# RJ45-2.net
KiCad netlist of a schematic drawn in Altium Designer
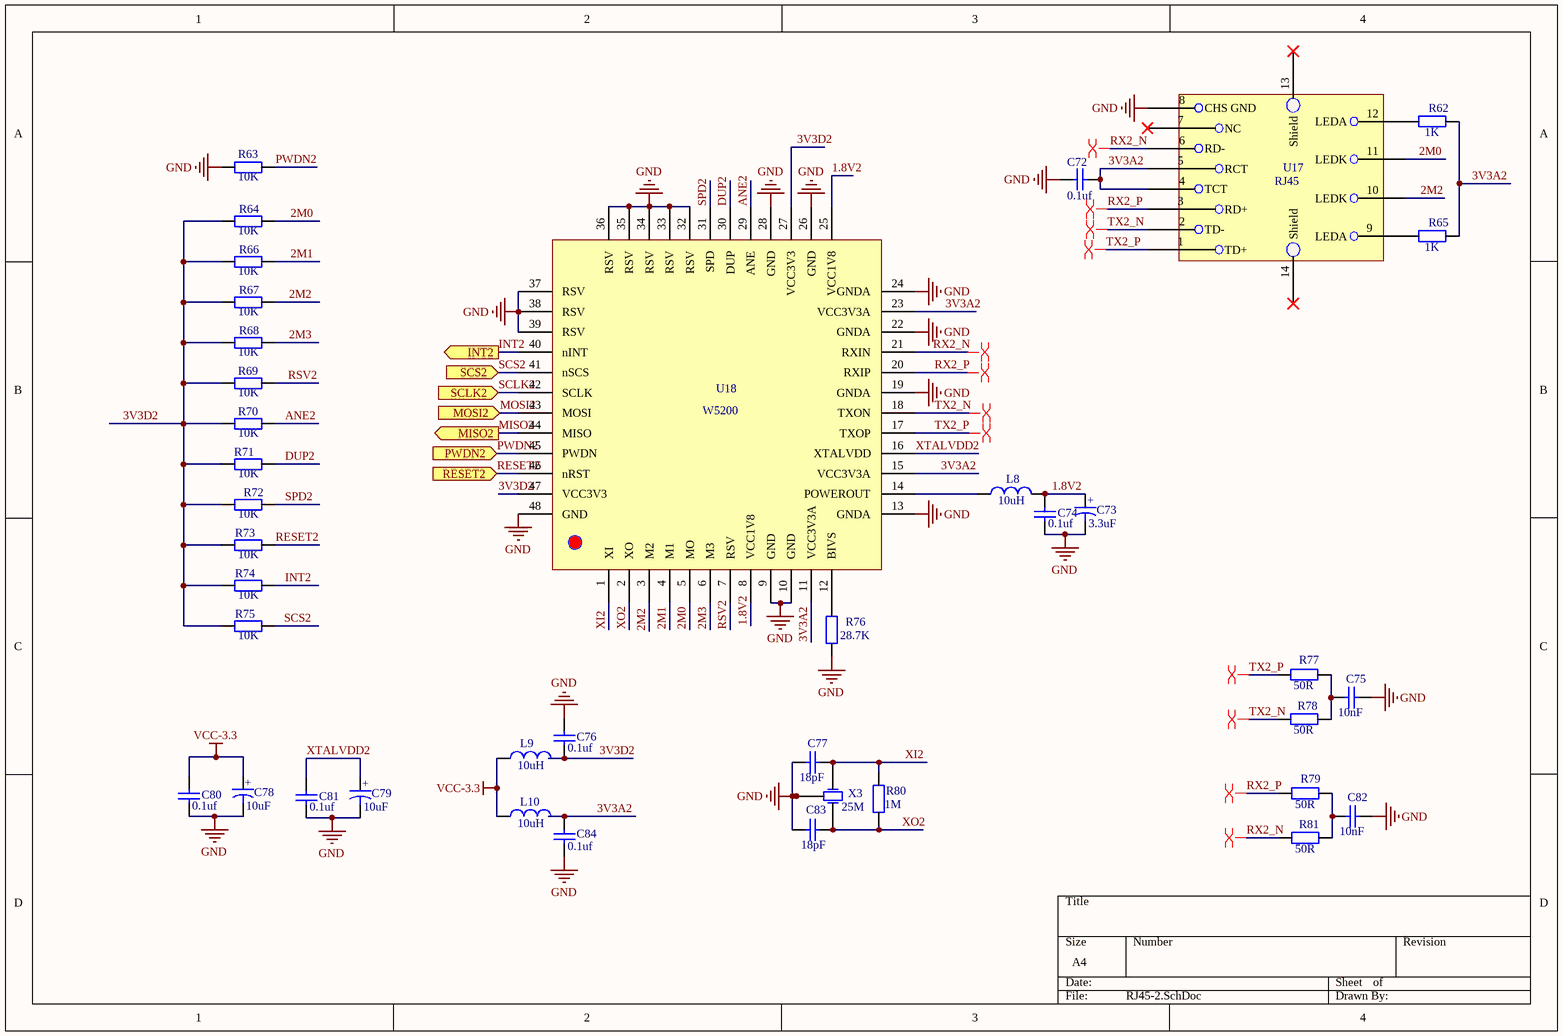
[diagram p0: RJ45-2.SchDoc]

(export (version "E")
  (design (tool "Eeschema 10.0.6"))
  (components
    (comp (ref "C72")
      (value "0.1uf")
      (footprint "0603")
      (fields (field (name "Comment") "Capacitor-0603"))
      (libsource (lib "原理图库") (part "Capacitor-0603"))
    )
    (comp (ref "C73")
      (value "3.3uF")
      (footprint "钽电容1206（A3216）")
      (fields (field (name "ALTIUM_UNNAMED_1") "+") (field (name "Comment") "电解电容"))
      (libsource (lib "原理图库") (part "电解电容"))
    )
    (comp (ref "C74")
      (value "0.1uf")
      (footprint "0603")
      (fields (field (name "Comment") "Capacitor-0603"))
      (libsource (lib "原理图库") (part "Capacitor-0603"))
    )
    (comp (ref "C75")
      (value "10nF")
      (footprint "0603")
      (fields (field (name "Comment") "Capacitor-0603"))
      (libsource (lib "原理图库") (part "Capacitor-0603"))
    )
    (comp (ref "C76")
      (value "0.1uf")
      (footprint "0603")
      (fields (field (name "Comment") "Capacitor-0603"))
      (libsource (lib "原理图库") (part "Capacitor-0603"))
    )
    (comp (ref "C77")
      (value "18pF")
      (footprint "0603")
      (fields (field (name "Comment") "Capacitor-0603"))
      (libsource (lib "原理图库") (part "Capacitor-0603"))
    )
    (comp (ref "C78")
      (value "10uF")
      (footprint "钽电容1206（A3216）")
      (fields (field (name "ALTIUM_UNNAMED_1") "+") (field (name "Comment") "电解电容"))
      (libsource (lib "原理图库") (part "电解电容"))
    )
    (comp (ref "C79")
      (value "10uF")
      (footprint "钽电容1206（A3216）")
      (fields (field (name "ALTIUM_UNNAMED_1") "+") (field (name "Comment") "电解电容"))
      (libsource (lib "原理图库") (part "电解电容"))
    )
    (comp (ref "C80")
      (value "0.1uf")
      (footprint "0603")
      (fields (field (name "Comment") "Capacitor-0603"))
      (libsource (lib "原理图库") (part "Capacitor-0603"))
    )
    (comp (ref "C81")
      (value "0.1uf")
      (footprint "0603")
      (fields (field (name "Comment") "Capacitor-0603"))
      (libsource (lib "原理图库") (part "Capacitor-0603"))
    )
    (comp (ref "C82")
      (value "10nF")
      (footprint "0603")
      (fields (field (name "Comment") "Capacitor-0603"))
      (libsource (lib "原理图库") (part "Capacitor-0603"))
    )
    (comp (ref "C83")
      (value "18pF")
      (footprint "0603")
      (fields (field (name "Comment") "Capacitor-0603"))
      (libsource (lib "原理图库") (part "Capacitor-0603"))
    )
    (comp (ref "C84")
      (value "0.1uf")
      (footprint "0603")
      (fields (field (name "Comment") "Capacitor-0603"))
      (libsource (lib "原理图库") (part "Capacitor-0603"))
    )
    (comp (ref "L8")
      (value "10uH")
      (footprint "0805")
      (fields (field (name "Comment") "Inductor"))
      (libsource (lib "原理图库") (part "Inductor"))
    )
    (comp (ref "L9")
      (value "10uH")
      (footprint "0805")
      (fields (field (name "Comment") "Inductor"))
      (libsource (lib "原理图库") (part "Inductor"))
    )
    (comp (ref "L10")
      (value "10uH")
      (footprint "0805")
      (fields (field (name "Comment") "Inductor"))
      (libsource (lib "原理图库") (part "Inductor"))
    )
    (comp (ref "R62")
      (value "1K")
      (footprint "0603")
      (fields (field (name "Comment") "Resistor-0603"))
      (libsource (lib "原理图库") (part "Resistor-0603"))
    )
    (comp (ref "R63")
      (value "10K")
      (footprint "0603")
      (fields (field (name "Comment") "Resistor-0603"))
      (libsource (lib "原理图库") (part "Resistor-0603"))
    )
    (comp (ref "R64")
      (value "10K")
      (footprint "0603")
      (fields (field (name "Comment") "Resistor-0603"))
      (libsource (lib "原理图库") (part "Resistor-0603"))
    )
    (comp (ref "R65")
      (value "1K")
      (footprint "0603")
      (fields (field (name "Comment") "Resistor-0603"))
      (libsource (lib "原理图库") (part "Resistor-0603"))
    )
    (comp (ref "R66")
      (value "10K")
      (footprint "0603")
      (fields (field (name "Comment") "Resistor-0603"))
      (libsource (lib "原理图库") (part "Resistor-0603"))
    )
    (comp (ref "R67")
      (value "10K")
      (footprint "0603")
      (fields (field (name "Comment") "Resistor-0603"))
      (libsource (lib "原理图库") (part "Resistor-0603"))
    )
    (comp (ref "R68")
      (value "10K")
      (footprint "0603")
      (fields (field (name "Comment") "Resistor-0603"))
      (libsource (lib "原理图库") (part "Resistor-0603"))
    )
    (comp (ref "R69")
      (value "10K")
      (footprint "0603")
      (fields (field (name "Comment") "Resistor-0603"))
      (libsource (lib "原理图库") (part "Resistor-0603"))
    )
    (comp (ref "R70")
      (value "10K")
      (footprint "0603")
      (fields (field (name "Comment") "Resistor-0603"))
      (libsource (lib "原理图库") (part "Resistor-0603"))
    )
    (comp (ref "R71")
      (value "10K")
      (footprint "0603")
      (fields (field (name "Comment") "Resistor-0603"))
      (libsource (lib "原理图库") (part "Resistor-0603"))
    )
    (comp (ref "R72")
      (value "10K")
      (footprint "0603")
      (fields (field (name "Comment") "Resistor-0603"))
      (libsource (lib "原理图库") (part "Resistor-0603"))
    )
    (comp (ref "R73")
      (value "10K")
      (footprint "0603")
      (fields (field (name "Comment") "Resistor-0603"))
      (libsource (lib "原理图库") (part "Resistor-0603"))
    )
    (comp (ref "R74")
      (value "10K")
      (footprint "0603")
      (fields (field (name "Comment") "Resistor-0603"))
      (libsource (lib "原理图库") (part "Resistor-0603"))
    )
    (comp (ref "R75")
      (value "10K")
      (footprint "0603")
      (fields (field (name "Comment") "Resistor-0603"))
      (libsource (lib "原理图库") (part "Resistor-0603"))
    )
    (comp (ref "R76")
      (value "28.7K")
      (footprint "0603")
      (fields (field (name "Comment") "Resistor-0603"))
      (libsource (lib "") (part "Resistor-0603_1"))
    )
    (comp (ref "R77")
      (value "50R")
      (footprint "0603")
      (fields (field (name "Comment") "Resistor-0603"))
      (libsource (lib "原理图库") (part "Resistor-0603"))
    )
    (comp (ref "R78")
      (value "50R")
      (footprint "0603")
      (fields (field (name "Comment") "Resistor-0603"))
      (libsource (lib "原理图库") (part "Resistor-0603"))
    )
    (comp (ref "R79")
      (value "50R")
      (footprint "0603")
      (fields (field (name "Comment") "Resistor-0603"))
      (libsource (lib "原理图库") (part "Resistor-0603"))
    )
    (comp (ref "R80")
      (value "1M")
      (footprint "0603")
      (fields (field (name "Comment") "Resistor-0603"))
      (libsource (lib "") (part "Resistor-0603_2"))
    )
    (comp (ref "R81")
      (value "50R")
      (footprint "0603")
      (fields (field (name "Comment") "Resistor-0603"))
      (libsource (lib "原理图库") (part "Resistor-0603"))
    )
    (comp (ref "U17")
      (value "RJ45")
      (footprint "RJ45")
      (fields (field (name "NAME") "RJ45"))
      (libsource (lib "原理图库") (part "RJ45"))
    )
    (comp (ref "U18")
      (value "W5200-Chip")
      (footprint "W5200-Chip")
      (fields (field (name "NAME") "W5200"))
      (libsource (lib "原理图库") (part "W5200-Chip"))
    )
    (comp (ref "X3")
      (value "25M")
      (footprint "3225无源晶振")
      (fields (field (name "Comment") "3225无源晶振"))
      (libsource (lib "原理图库") (part "3225无源晶振"))
    )
  )
  (nets
    (net (code "1") (name "/1.8V2") (class "Default")
      (node (ref "C73") (pin "2") (pinfunction "2_2") (pintype "passive"))
      (node (ref "C74") (pin "2") (pinfunction "2_2") (pintype "passive"))
      (node (ref "L8") (pin "2") (pinfunction "2_2") (pintype "passive"))
      (node (ref "U18") (pin "25") (pinfunction "VCC1V8_25") (pintype "passive"))
      (node (ref "U18") (pin "8") (pinfunction "VCC1V8_8") (pintype "passive"))
    )
    (net (code "2") (name "/2M0") (class "Default")
      (node (ref "R64") (pin "2") (pinfunction "2_2") (pintype "passive"))
      (node (ref "U17") (pin "11") (pinfunction "LEDK_11") (pintype "passive"))
      (node (ref "U18") (pin "5") (pinfunction "MO_5") (pintype "passive"))
    )
    (net (code "3") (name "/2M1") (class "Default")
      (node (ref "R66") (pin "2") (pinfunction "2_2") (pintype "passive"))
      (node (ref "U18") (pin "4") (pinfunction "M1_4") (pintype "passive"))
    )
    (net (code "4") (name "/2M2") (class "Default")
      (node (ref "R67") (pin "2") (pinfunction "2_2") (pintype "passive"))
      (node (ref "U17") (pin "10") (pinfunction "LEDK_10") (pintype "passive"))
      (node (ref "U18") (pin "3") (pinfunction "M2_3") (pintype "passive"))
    )
    (net (code "5") (name "/2M3") (class "Default")
      (node (ref "R68") (pin "2") (pinfunction "2_2") (pintype "passive"))
      (node (ref "U18") (pin "6") (pinfunction "M3_6") (pintype "passive"))
    )
    (net (code "6") (name "/3V3A2") (class "Default")
      (node (ref "C72") (pin "1") (pinfunction "1_1") (pintype "passive"))
      (node (ref "C84") (pin "1") (pinfunction "1_1") (pintype "passive"))
      (node (ref "L10") (pin "2") (pinfunction "2_2") (pintype "passive"))
      (node (ref "R62") (pin "2") (pinfunction "2_2") (pintype "passive"))
      (node (ref "R65") (pin "2") (pinfunction "2_2") (pintype "passive"))
      (node (ref "U17") (pin "4") (pinfunction "TCT_4") (pintype "passive"))
      (node (ref "U17") (pin "5") (pinfunction "RCT_5") (pintype "passive"))
      (node (ref "U18") (pin "11") (pinfunction "VCC3V3A_11") (pintype "passive"))
      (node (ref "U18") (pin "15") (pinfunction "VCC3V3A_15") (pintype "passive"))
      (node (ref "U18") (pin "23") (pinfunction "VCC3V3A_23") (pintype "passive"))
    )
    (net (code "7") (name "/3V3D2") (class "Default")
      (node (ref "C76") (pin "1") (pinfunction "1_1") (pintype "passive"))
      (node (ref "L9") (pin "2") (pinfunction "2_2") (pintype "passive"))
      (node (ref "R64") (pin "1") (pinfunction "1_1") (pintype "passive"))
      (node (ref "R66") (pin "1") (pinfunction "1_1") (pintype "passive"))
      (node (ref "R67") (pin "1") (pinfunction "1_1") (pintype "passive"))
      (node (ref "R68") (pin "1") (pinfunction "1_1") (pintype "passive"))
      (node (ref "R69") (pin "1") (pinfunction "1_1") (pintype "passive"))
      (node (ref "R70") (pin "1") (pinfunction "1_1") (pintype "passive"))
      (node (ref "R71") (pin "1") (pinfunction "1_1") (pintype "passive"))
      (node (ref "R72") (pin "1") (pinfunction "1_1") (pintype "passive"))
      (node (ref "R73") (pin "1") (pinfunction "1_1") (pintype "passive"))
      (node (ref "R74") (pin "1") (pinfunction "1_1") (pintype "passive"))
      (node (ref "R75") (pin "1") (pinfunction "1_1") (pintype "passive"))
      (node (ref "U18") (pin "27") (pinfunction "VCC3V3_27") (pintype "passive"))
      (node (ref "U18") (pin "47") (pinfunction "VCC3V3_47") (pintype "passive"))
    )
    (net (code "8") (name "/ANE2") (class "Default")
      (node (ref "R70") (pin "2") (pinfunction "2_2") (pintype "passive"))
      (node (ref "U18") (pin "29") (pinfunction "ANE_29") (pintype "passive"))
    )
    (net (code "9") (name "/DUP2") (class "Default")
      (node (ref "R71") (pin "2") (pinfunction "2_2") (pintype "passive"))
      (node (ref "U18") (pin "30") (pinfunction "DUP_30") (pintype "passive"))
    )
    (net (code "10") (name "/INT2") (class "Default")
      (node (ref "R74") (pin "2") (pinfunction "2_2") (pintype "passive"))
      (node (ref "U18") (pin "40") (pinfunction "nINT_40") (pintype "passive"))
    )
    (net (code "11") (name "/MISO2") (class "Default")
      (node (ref "U18") (pin "44") (pinfunction "MISO_44") (pintype "passive"))
    )
    (net (code "12") (name "/MOSI2") (class "Default")
      (node (ref "U18") (pin "43") (pinfunction "MOSI_43") (pintype "passive"))
    )
    (net (code "13") (name "/PWDN2") (class "Default")
      (node (ref "R63") (pin "2") (pinfunction "2_2") (pintype "passive"))
      (node (ref "U18") (pin "45") (pinfunction "PWDN_45") (pintype "passive"))
    )
    (net (code "14") (name "/RESET2") (class "Default")
      (node (ref "R73") (pin "2") (pinfunction "2_2") (pintype "passive"))
      (node (ref "U18") (pin "46") (pinfunction "nRST_46") (pintype "passive"))
    )
    (net (code "15") (name "/RSV2") (class "Default")
      (node (ref "R69") (pin "2") (pinfunction "2_2") (pintype "passive"))
      (node (ref "U18") (pin "7") (pinfunction "RSV_7") (pintype "passive"))
    )
    (net (code "16") (name "/RX2_N") (class "Default")
      (node (ref "R81") (pin "1") (pinfunction "1_1") (pintype "passive"))
      (node (ref "U17") (pin "6") (pinfunction "RD-_6") (pintype "passive"))
      (node (ref "U18") (pin "21") (pinfunction "RXIN_21") (pintype "passive"))
    )
    (net (code "17") (name "/RX2_P") (class "Default")
      (node (ref "R79") (pin "1") (pinfunction "1_1") (pintype "passive"))
      (node (ref "U17") (pin "3") (pinfunction "RD+_3") (pintype "passive"))
      (node (ref "U18") (pin "20") (pinfunction "RXIP_20") (pintype "passive"))
    )
    (net (code "18") (name "/SCLK2") (class "Default")
      (node (ref "U18") (pin "42") (pinfunction "SCLK_42") (pintype "passive"))
    )
    (net (code "19") (name "/SCS2") (class "Default")
      (node (ref "R75") (pin "2") (pinfunction "2_2") (pintype "passive"))
      (node (ref "U18") (pin "41") (pinfunction "nSCS_41") (pintype "passive"))
    )
    (net (code "20") (name "/SPD2") (class "Default")
      (node (ref "R72") (pin "2") (pinfunction "2_2") (pintype "passive"))
      (node (ref "U18") (pin "31") (pinfunction "SPD_31") (pintype "passive"))
    )
    (net (code "21") (name "/TX2_N") (class "Default")
      (node (ref "R78") (pin "1") (pinfunction "1_1") (pintype "passive"))
      (node (ref "U17") (pin "2") (pinfunction "TD-_2") (pintype "passive"))
      (node (ref "U18") (pin "18") (pinfunction "TXON_18") (pintype "passive"))
    )
    (net (code "22") (name "/TX2_P") (class "Default")
      (node (ref "R77") (pin "1") (pinfunction "1_1") (pintype "passive"))
      (node (ref "U17") (pin "1") (pinfunction "TD+_1") (pintype "passive"))
      (node (ref "U18") (pin "17") (pinfunction "TXOP_17") (pintype "passive"))
    )
    (net (code "23") (name "/XI2") (class "Default")
      (node (ref "C77") (pin "2") (pinfunction "2_2") (pintype "passive"))
      (node (ref "R80") (pin "1") (pinfunction "1_1") (pintype "passive"))
      (node (ref "U18") (pin "1") (pinfunction "XI_1") (pintype "passive"))
      (node (ref "X3") (pin "1") (pinfunction "OSC1_1") (pintype "passive"))
    )
    (net (code "24") (name "/XO2") (class "Default")
      (node (ref "C83") (pin "2") (pinfunction "2_2") (pintype "passive"))
      (node (ref "R80") (pin "2") (pinfunction "2_2") (pintype "passive"))
      (node (ref "U18") (pin "2") (pinfunction "XO_2") (pintype "passive"))
      (node (ref "X3") (pin "3") (pinfunction "OSC2_3") (pintype "passive"))
    )
    (net (code "25") (name "/XTALVDD2") (class "Default")
      (node (ref "C79") (pin "2") (pinfunction "2_2") (pintype "passive"))
      (node (ref "C81") (pin "2") (pinfunction "2_2") (pintype "passive"))
      (node (ref "U18") (pin "16") (pinfunction "XTALVDD_16") (pintype "passive"))
    )
    (net (code "26") (name "GND") (class "Default")
      (node (ref "C72") (pin "2") (pinfunction "2_2") (pintype "passive"))
      (node (ref "C73") (pin "1") (pinfunction "1_1") (pintype "passive"))
      (node (ref "C74") (pin "1") (pinfunction "1_1") (pintype "passive"))
      (node (ref "C75") (pin "2") (pinfunction "2_2") (pintype "passive"))
      (node (ref "C76") (pin "2") (pinfunction "2_2") (pintype "passive"))
      (node (ref "C77") (pin "1") (pinfunction "1_1") (pintype "passive"))
      (node (ref "C78") (pin "1") (pinfunction "1_1") (pintype "passive"))
      (node (ref "C79") (pin "1") (pinfunction "1_1") (pintype "passive"))
      (node (ref "C80") (pin "1") (pinfunction "1_1") (pintype "passive"))
      (node (ref "C81") (pin "1") (pinfunction "1_1") (pintype "passive"))
      (node (ref "C82") (pin "2") (pinfunction "2_2") (pintype "passive"))
      (node (ref "C83") (pin "1") (pinfunction "1_1") (pintype "passive"))
      (node (ref "C84") (pin "2") (pinfunction "2_2") (pintype "passive"))
      (node (ref "R63") (pin "1") (pinfunction "1_1") (pintype "passive"))
      (node (ref "R76") (pin "1") (pinfunction "1_1") (pintype "passive"))
      (node (ref "U17") (pin "8") (pinfunction "CHS_GND_8") (pintype "passive"))
      (node (ref "U18") (pin "10") (pinfunction "GND_10") (pintype "passive"))
      (node (ref "U18") (pin "13") (pinfunction "GNDA_13") (pintype "passive"))
      (node (ref "U18") (pin "19") (pinfunction "GNDA_19") (pintype "passive"))
      (node (ref "U18") (pin "22") (pinfunction "GNDA_22") (pintype "passive"))
      (node (ref "U18") (pin "24") (pinfunction "GNDA_24") (pintype "passive"))
      (node (ref "U18") (pin "26") (pinfunction "GND_26") (pintype "passive"))
      (node (ref "U18") (pin "28") (pinfunction "GND_28") (pintype "passive"))
      (node (ref "U18") (pin "32") (pinfunction "RSV_32") (pintype "passive"))
      (node (ref "U18") (pin "33") (pinfunction "RSV_33") (pintype "passive"))
      (node (ref "U18") (pin "34") (pinfunction "RSV_34") (pintype "passive"))
      (node (ref "U18") (pin "35") (pinfunction "RSV_35") (pintype "passive"))
      (node (ref "U18") (pin "36") (pinfunction "RSV_36") (pintype "passive"))
      (node (ref "U18") (pin "37") (pinfunction "RSV_37") (pintype "passive"))
      (node (ref "U18") (pin "38") (pinfunction "RSV_38") (pintype "passive"))
      (node (ref "U18") (pin "39") (pinfunction "RSV_39") (pintype "passive"))
      (node (ref "U18") (pin "48") (pinfunction "GND_48") (pintype "passive"))
      (node (ref "U18") (pin "9") (pinfunction "GND_9") (pintype "passive"))
      (node (ref "X3") (pin "2") (pinfunction "GND_2") (pintype "passive"))
      (node (ref "X3") (pin "4") (pinfunction "GND_4") (pintype "passive"))
    )
    (net (code "27") (name "Net-(C75-Pad1)") (class "Default")
      (node (ref "C75") (pin "1") (pinfunction "1_1") (pintype "passive"))
      (node (ref "R77") (pin "2") (pinfunction "2_2") (pintype "passive"))
      (node (ref "R78") (pin "2") (pinfunction "2_2") (pintype "passive"))
    )
    (net (code "28") (name "Net-(C82-Pad1)") (class "Default")
      (node (ref "C82") (pin "1") (pinfunction "1_1") (pintype "passive"))
      (node (ref "R79") (pin "2") (pinfunction "2_2") (pintype "passive"))
      (node (ref "R81") (pin "2") (pinfunction "2_2") (pintype "passive"))
    )
    (net (code "29") (name "Net-(R62-Pad1)") (class "Default")
      (node (ref "R62") (pin "1") (pinfunction "1_1") (pintype "passive"))
      (node (ref "U17") (pin "12") (pinfunction "LEDA_12") (pintype "passive"))
    )
    (net (code "30") (name "Net-(R65-Pad1)") (class "Default")
      (node (ref "R65") (pin "1") (pinfunction "1_1") (pintype "passive"))
      (node (ref "U17") (pin "9") (pinfunction "LEDA_9") (pintype "passive"))
    )
    (net (code "31") (name "Net-(U18-BIVS)") (class "Default")
      (node (ref "R76") (pin "2") (pinfunction "2_2") (pintype "passive"))
      (node (ref "U18") (pin "12") (pinfunction "BIVS_12") (pintype "passive"))
    )
    (net (code "32") (name "Net-(U18-POWEROUT)") (class "Default")
      (node (ref "L8") (pin "1") (pinfunction "1_1") (pintype "passive"))
      (node (ref "U18") (pin "14") (pinfunction "POWEROUT_14") (pintype "passive"))
    )
    (net (code "33") (name "VCC-3.3") (class "Default")
      (node (ref "C78") (pin "2") (pinfunction "2_2") (pintype "passive"))
      (node (ref "C80") (pin "2") (pinfunction "2_2") (pintype "passive"))
      (node (ref "L10") (pin "1") (pinfunction "1_1") (pintype "passive"))
      (node (ref "L9") (pin "1") (pinfunction "1_1") (pintype "passive"))
    )
    (net (code "34") (name "unconnected-(U17-NC-Pad7)") (class "Default")
      (node (ref "U17") (pin "7") (pinfunction "NC_7") (pintype "passive+no_connect"))
    )
    (net (code "35") (name "unconnected-(U17-Shield-Pad13)") (class "Default")
      (node (ref "U17") (pin "13") (pinfunction "Shield_13") (pintype "passive+no_connect"))
    )
    (net (code "36") (name "unconnected-(U17-Shield-Pad14)") (class "Default")
      (node (ref "U17") (pin "14") (pinfunction "Shield_14") (pintype "passive+no_connect"))
    )
  )
)
